# LNA-SMA.net
KiCad netlist of a schematic drawn in EAGLE
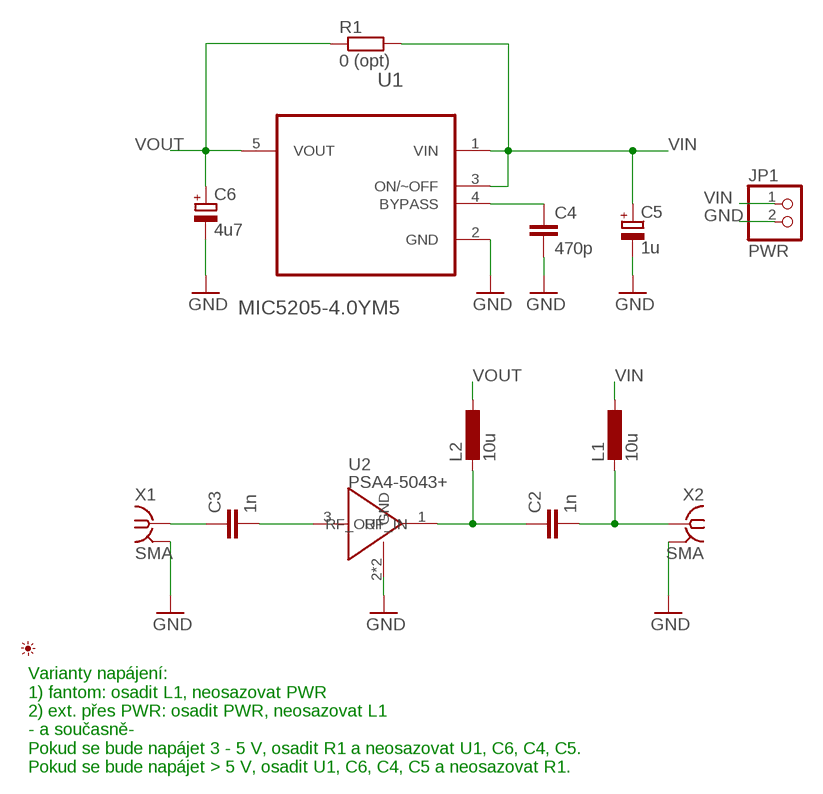
[diagram p0: schematic, sheet 1]

(export (version "E")
  (design (tool "Eeschema 10.0.6"))
  (components
    (comp (ref "C2")
      (value "1n")
      (footprint "eagle-import:C0603")
      (libsource (lib "eagle-import") (part "C-EUC0603"))
    )
    (comp (ref "C3")
      (value "1n")
      (footprint "eagle-import:C0603")
      (libsource (lib "eagle-import") (part "C-EUC0603"))
    )
    (comp (ref "C4")
      (value "470p")
      (footprint "eagle-import:C0603")
      (libsource (lib "eagle-import") (part "C-EUC0603"))
    )
    (comp (ref "C5")
      (value "1u")
      (footprint "eagle-import:SMC_A")
      (libsource (lib "eagle-import") (part "CPOL-EUSMCA"))
    )
    (comp (ref "C6")
      (value "4u7")
      (footprint "eagle-import:SMC_A")
      (libsource (lib "eagle-import") (part "CPOL-EUSMCA"))
    )
    (comp (ref "JP1")
      (value "PWR")
      (footprint "eagle-import:1X02")
      (libsource (lib "eagle-import") (part "PINHD-1X2"))
    )
    (comp (ref "L1")
      (value "10u")
      (footprint "eagle-import:L2012C")
      (libsource (lib "eagle-import") (part "L-EUL2012C"))
    )
    (comp (ref "L2")
      (value "10u")
      (footprint "eagle-import:L2012C")
      (libsource (lib "eagle-import") (part "L-EUL2012C"))
    )
    (comp (ref "R1")
      (value "0 (opt)")
      (footprint "eagle-import:R0603")
      (libsource (lib "eagle-import") (part "R-EU_R0603"))
    )
    (comp (ref "U$1")
      (value "PICTO_1")
      (footprint "eagle-import:PICTO_1")
      (libsource (lib "eagle-import") (part "PICTO_1"))
    )
    (comp (ref "U1")
      (value "MIC5205-4.0YM5")
      (footprint "eagle-import:SOT95P280X145-5N")
      (fields (field (name "MPN") "LP2985A-18DBVJ"))
      (libsource (lib "eagle-import") (part "LP2985A-18DBVJ"))
    )
    (comp (ref "U2")
      (value "PSA4-5043+")
      (footprint "eagle-import:INF-SOT343_V_1PRIMARY")
      (libsource (lib "eagle-import") (part "PSA4-5043+"))
    )
    (comp (ref "X1")
      (value "SMA")
      (footprint "eagle-import:J502-ND-142-0701-801_806")
      (fields (field (name "MF") "JOHNSON COMPONENTS") (field (name "MPN") "142-0701-801"))
      (libsource (lib "eagle-import") (part "SMA-142-0701-801/806"))
    )
    (comp (ref "X2")
      (value "SMA")
      (footprint "eagle-import:J502-ND-142-0701-801_806")
      (fields (field (name "MF") "JOHNSON COMPONENTS") (field (name "MPN") "142-0701-801"))
      (libsource (lib "eagle-import") (part "SMA-142-0701-801/806"))
    )
  )
  (nets
    (net (code "1") (name "/VIN") (class "Default")
      (node (ref "C5") (pin "+") (pinfunction "+_+") (pintype "passive"))
      (node (ref "JP1") (pin "1") (pinfunction "1_1") (pintype "passive"))
      (node (ref "L1") (pin "1") (pinfunction "1_1") (pintype "passive"))
      (node (ref "R1") (pin "2") (pinfunction "2_2") (pintype "passive"))
      (node (ref "U1") (pin "1") (pinfunction "VIN_1") (pintype "input"))
      (node (ref "U1") (pin "3") (pinfunction "ON/~{OFF}_3") (pintype "input"))
    )
    (net (code "2") (name "/VOUT") (class "Default")
      (node (ref "C6") (pin "+") (pinfunction "+_+") (pintype "passive"))
      (node (ref "L2") (pin "1") (pinfunction "1_1") (pintype "passive"))
      (node (ref "R1") (pin "1") (pinfunction "1_1") (pintype "passive"))
      (node (ref "U1") (pin "5") (pinfunction "VOUT_5") (pintype "output"))
    )
    (net (code "3") (name "GND") (class "Default")
      (node (ref "C4") (pin "2") (pinfunction "2_2") (pintype "passive"))
      (node (ref "C5") (pin "-") (pinfunction "-_-") (pintype "passive"))
      (node (ref "C6") (pin "-") (pinfunction "-_-") (pintype "passive"))
      (node (ref "JP1") (pin "2") (pinfunction "2_2") (pintype "passive"))
      (node (ref "U1") (pin "2") (pinfunction "GND_2") (pintype "passive"))
      (node (ref "U2") (pin "2") (pinfunction "GND_2") (pintype "power_in"))
      (node (ref "U2") (pin "4") (pinfunction "GND_4") (pintype "power_in"))
      (node (ref "X1") (pin "G@1") (pinfunction "2_G@1") (pintype "passive"))
      (node (ref "X1") (pin "G@2") (pinfunction "2_G@2") (pintype "passive"))
      (node (ref "X1") (pin "G@3") (pinfunction "2_G@3") (pintype "passive"))
      (node (ref "X1") (pin "G@4") (pinfunction "2_G@4") (pintype "passive"))
      (node (ref "X2") (pin "G@1") (pinfunction "2_G@1") (pintype "passive"))
      (node (ref "X2") (pin "G@2") (pinfunction "2_G@2") (pintype "passive"))
      (node (ref "X2") (pin "G@3") (pinfunction "2_G@3") (pintype "passive"))
      (node (ref "X2") (pin "G@4") (pinfunction "2_G@4") (pintype "passive"))
    )
    (net (code "4") (name "Net-(C2-Pad2)") (class "Default")
      (node (ref "C2") (pin "2") (pinfunction "2_2") (pintype "passive"))
      (node (ref "L1") (pin "2") (pinfunction "2_2") (pintype "passive"))
      (node (ref "X2") (pin "1") (pinfunction "1_1") (pintype "passive"))
    )
    (net (code "5") (name "Net-(C3-Pad1)") (class "Default")
      (node (ref "C3") (pin "1") (pinfunction "1_1") (pintype "passive"))
      (node (ref "X1") (pin "1") (pinfunction "1_1") (pintype "passive"))
    )
    (net (code "6") (name "Net-(U1-BYPASS)") (class "Default")
      (node (ref "C4") (pin "1") (pinfunction "1_1") (pintype "passive"))
      (node (ref "U1") (pin "4") (pinfunction "BYPASS_4") (pintype "input"))
    )
    (net (code "7") (name "Net-(U2-RF_IN)") (class "Default")
      (node (ref "C3") (pin "2") (pinfunction "2_2") (pintype "passive"))
      (node (ref "U2") (pin "3") (pinfunction "RF_IN_3") (pintype "input"))
    )
    (net (code "8") (name "Net-(U2-RF_OUT)") (class "Default")
      (node (ref "C2") (pin "1") (pinfunction "1_1") (pintype "passive"))
      (node (ref "L2") (pin "2") (pinfunction "2_2") (pintype "passive"))
      (node (ref "U2") (pin "1") (pinfunction "RF_OUT_1") (pintype "output"))
    )
  )
)
